# Latching_2.net
KiCad netlist of a schematic drawn in Altium Designer
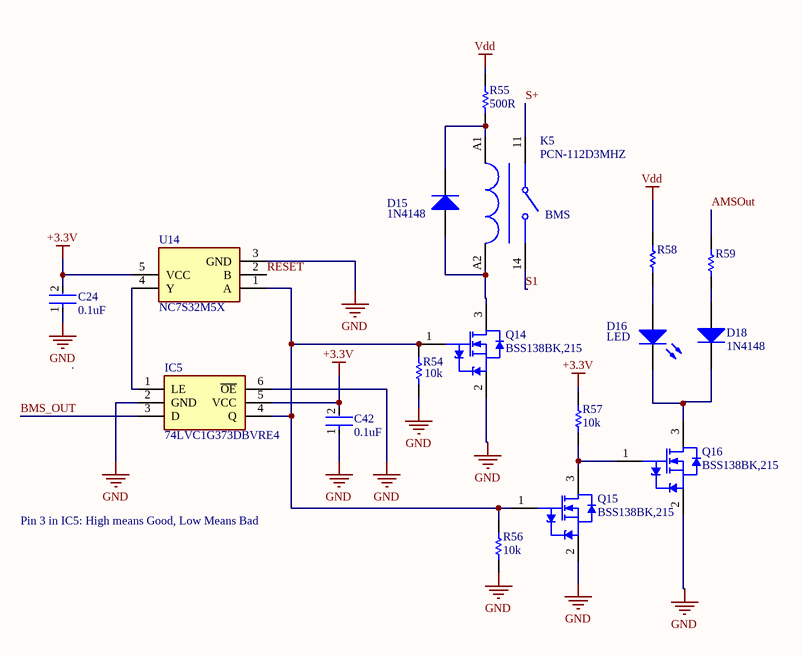
[diagram p0: Latching 2.SchDoc]

(export (version "E")
  (design (tool "Eeschema 10.0.6"))
  (components
    (comp (ref "C24")
      (value "0.1uF")
      (footprint "FP-C0603-CJ-MFG")
      (description "CAP CER 0.1UF 50V X7R 0603")
      (fields (field (name "MANUFACTURER PART NUMBER") "C0603X104K5RACTU") (field (name "VOLTAGE") "50V"))
      (libsource (lib "Altium Content Vault") (part "11868f565c42a9108669ba33697ecf6"))
    )
    (comp (ref "C42")
      (value "0.1uF")
      (footprint "FP-C0603-CJ-MFG")
      (description "CAP CER 0.1UF 50V X7R 0603")
      (fields (field (name "MANUFACTURER PART NUMBER") "C0603X104K5RACTU") (field (name "VOLTAGE") "50V"))
      (libsource (lib "Altium Content Vault") (part "11868f565c42a9108669ba33697ecf6"))
    )
    (comp (ref "D15")
      (value "1N4148")
      (footprint "DIOD-SOD123-2_V")
      (description "DIODE GEN PURP 100V 300MA SOD123")
      (fields (field (name "VOLTAGE") "100V"))
      (libsource (lib "Diodes") (part "1N4148W-7-F"))
    )
    (comp (ref "D16")
      (value "LED")
      (footprint "1206_A")
      (description "WURTH ELEKTRONIK   150120SS75000   LED, 1206, SUP. RED, 60MCD, 630NM")
      (libsource (lib "LED") (part "150120SS75000"))
    )
    (comp (ref "D18")
      (value "1N4148")
      (footprint "DIOD-SOD123-2_V")
      (description "DIODE GEN PURP 100V 300MA SOD123")
      (fields (field (name "VOLTAGE") "100V"))
      (libsource (lib "Diodes") (part "1N4148W-7-F"))
    )
    (comp (ref "IC5")
      (value "74LVC1G373DBVRE4")
      (footprint "SOT95P280X145-6N")
      (description "Integrated Circuit")
      (libsource (lib "*") (part "74LVC1G373DBVRE4"))
    )
    (comp (ref "K5")
      (value "PCN-112D3MHZ")
      (footprint "PCN-112D3MHZ")
      (description "Relay")
      (libsource (lib "SamacSys") (part "PCN-112D3MHZ"))
    )
    (comp (ref "Q14")
      (value "BSS138BK,215")
      (footprint "NXP-SOT23_N")
      (description "N-Channel Trench MOSFET, 60 V, 0.36 A, -55 to 150 degC, 3-Pin SOT23, Tape and Reel")
      (fields (field (name "MANUFACTURER") "NXP Semiconductors"))
      (libsource (lib "Altium Content Vault") (part "NXP-NMOS-GSD-3"))
    )
    (comp (ref "Q15")
      (value "BSS138BK,215")
      (footprint "NXP-SOT23_N")
      (description "N-Channel Trench MOSFET, 60 V, 0.36 A, -55 to 150 degC, 3-Pin SOT23, Tape and Reel")
      (fields (field (name "MANUFACTURER") "NXP Semiconductors"))
      (libsource (lib "Altium Content Vault") (part "NXP-NMOS-GSD-3"))
    )
    (comp (ref "Q16")
      (value "BSS138BK,215")
      (footprint "NXP-SOT23_N")
      (description "N-Channel Trench MOSFET, 60 V, 0.36 A, -55 to 150 degC, 3-Pin SOT23, Tape and Reel")
      (fields (field (name "MANUFACTURER") "NXP Semiconductors"))
      (libsource (lib "Altium Content Vault") (part "NXP-NMOS-GSD-3"))
    )
    (comp (ref "R54")
      (value "10k")
      (footprint "RESC1608X55N")
      (description "10k E0805 1% 1/8W")
      (fields (field (name "TOLERANCE") "5%"))
      (libsource (lib "Resistors") (part "RC0805JR-0710KL"))
    )
    (comp (ref "R55")
      (value "500R")
      (footprint "RESC1608X55N")
      (description "10k E0805 1% 1/8W")
      (fields (field (name "TOLERANCE") "5%"))
      (libsource (lib "Resistors") (part "RC0805JR-0710KL"))
    )
    (comp (ref "R56")
      (value "10k")
      (footprint "RESC1608X55N")
      (description "10k E0805 1% 1/8W")
      (fields (field (name "TOLERANCE") "5%"))
      (libsource (lib "Resistors") (part "RC0805JR-0710KL"))
    )
    (comp (ref "R57")
      (value "10k")
      (footprint "RESC1608X55N")
      (description "10k E0805 1% 1/8W")
      (fields (field (name "TOLERANCE") "5%"))
      (libsource (lib "Resistors") (part "RC0805JR-0710KL"))
    )
    (comp (ref "R58")
      (value "CRCW2512649RFKEG")
      (footprint "Resistor__E2512")
      (description "RES SMD 649 OHM 1% 1W 2512")
      (fields (field (name "TOLERANCE") "1%"))
      (libsource (lib "Resistors") (part "CRCW2512649RFKEG"))
    )
    (comp (ref "R59")
      (value "CRCW2512649RFKEG")
      (footprint "Resistor__E2512")
      (description "RES SMD 649 OHM 1% 1W 2512")
      (fields (field (name "TOLERANCE") "1%"))
      (libsource (lib "Resistors") (part "CRCW2512649RFKEG"))
    )
    (comp (ref "U14")
      (value "NC7S32M5X")
      (footprint "SOT95P275X110-5N")
      (description "OR GATEEEE")
      (libsource (lib "SamacSys") (part "NC7S32M5X"))
    )
  )
  (nets
    (net (code "1") (name "+3.3V") (class "Default")
      (node (ref "C24") (pin "2") (pinfunction "2_2") (pintype "passive"))
      (node (ref "C42") (pin "2") (pinfunction "2_2") (pintype "passive"))
      (node (ref "IC5") (pin "5") (pinfunction "VCC_5") (pintype "passive"))
      (node (ref "R57") (pin "2") (pinfunction "2_2") (pintype "passive"))
      (node (ref "U14") (pin "5") (pinfunction "VCC_5") (pintype "passive"))
    )
    (net (code "2") (name "/AMSOut") (class "Default")
      (node (ref "R59") (pin "2") (pinfunction "2_2") (pintype "passive"))
    )
    (net (code "3") (name "/BMS_OUT") (class "Default")
      (node (ref "IC5") (pin "3") (pinfunction "D_3") (pintype "passive"))
    )
    (net (code "4") (name "/RESET") (class "Default")
      (node (ref "U14") (pin "2") (pinfunction "B_2") (pintype "passive"))
    )
    (net (code "5") (name "/S+") (class "Default") (node (ref "K5") (pin "11") (pintype "passive")))
    (net (code "6") (name "/S1") (class "Default") (node (ref "K5") (pin "14") (pintype "passive")))
    (net (code "7") (name "GND") (class "Default")
      (node (ref "C24") (pin "1") (pinfunction "1_1") (pintype "passive"))
      (node (ref "C42") (pin "1") (pinfunction "1_1") (pintype "passive"))
      (node (ref "IC5") (pin "2") (pinfunction "GND_2") (pintype "passive"))
      (node (ref "IC5") (pin "6") (pinfunction "~{OE}_6") (pintype "passive"))
      (node (ref "Q14") (pin "2") (pinfunction "S_2") (pintype "passive"))
      (node (ref "Q15") (pin "2") (pinfunction "S_2") (pintype "passive"))
      (node (ref "Q16") (pin "2") (pinfunction "S_2") (pintype "passive"))
      (node (ref "R54") (pin "1") (pinfunction "1_1") (pintype "passive"))
      (node (ref "R56") (pin "1") (pinfunction "1_1") (pintype "passive"))
      (node (ref "U14") (pin "3") (pinfunction "GND_3") (pintype "passive"))
    )
    (net (code "8") (name "Net-(D15-A)") (class "Default")
      (node (ref "D15") (pin "1") (pinfunction "A_1") (pintype "passive"))
      (node (ref "K5") (pin "A2") (pintype "passive"))
      (node (ref "Q14") (pin "3") (pinfunction "D_3") (pintype "passive"))
    )
    (net (code "9") (name "Net-(D15-K)") (class "Default")
      (node (ref "D15") (pin "2") (pinfunction "K_2") (pintype "passive"))
      (node (ref "K5") (pin "A1") (pintype "passive"))
      (node (ref "R55") (pin "1") (pinfunction "1_1") (pintype "passive"))
    )
    (net (code "10") (name "Net-(D16-A)") (class "Default")
      (node (ref "D16") (pin "2") (pinfunction "A_2") (pintype "passive"))
      (node (ref "R58") (pin "1") (pinfunction "1_1") (pintype "passive"))
    )
    (net (code "11") (name "Net-(D16-K)") (class "Default")
      (node (ref "D16") (pin "1") (pinfunction "K_1") (pintype "passive"))
      (node (ref "D18") (pin "2") (pinfunction "K_2") (pintype "passive"))
      (node (ref "Q16") (pin "3") (pinfunction "D_3") (pintype "passive"))
    )
    (net (code "12") (name "Net-(D18-A)") (class "Default")
      (node (ref "D18") (pin "1") (pinfunction "A_1") (pintype "passive"))
      (node (ref "R59") (pin "1") (pinfunction "1_1") (pintype "passive"))
    )
    (net (code "13") (name "Net-(IC5-LE)") (class "Default")
      (node (ref "IC5") (pin "1") (pinfunction "LE_1") (pintype "passive"))
      (node (ref "U14") (pin "4") (pinfunction "Y_4") (pintype "passive"))
    )
    (net (code "14") (name "Net-(IC5-Q)") (class "Default")
      (node (ref "IC5") (pin "4") (pinfunction "Q_4") (pintype "passive"))
      (node (ref "Q14") (pin "1") (pinfunction "G_1") (pintype "passive"))
      (node (ref "Q15") (pin "1") (pinfunction "G_1") (pintype "passive"))
      (node (ref "R54") (pin "2") (pinfunction "2_2") (pintype "passive"))
      (node (ref "R56") (pin "2") (pinfunction "2_2") (pintype "passive"))
      (node (ref "U14") (pin "1") (pinfunction "A_1") (pintype "passive"))
    )
    (net (code "15") (name "Net-(Q15-D)") (class "Default")
      (node (ref "Q15") (pin "3") (pinfunction "D_3") (pintype "passive"))
      (node (ref "Q16") (pin "1") (pinfunction "G_1") (pintype "passive"))
      (node (ref "R57") (pin "1") (pinfunction "1_1") (pintype "passive"))
    )
    (net (code "16") (name "Vdd") (class "Default")
      (node (ref "R55") (pin "2") (pinfunction "2_2") (pintype "passive"))
      (node (ref "R58") (pin "2") (pinfunction "2_2") (pintype "passive"))
    )
  )
)
